# w5-MIDI_v03_rev4_4.net
KiCad netlist of a schematic drawn in EAGLE
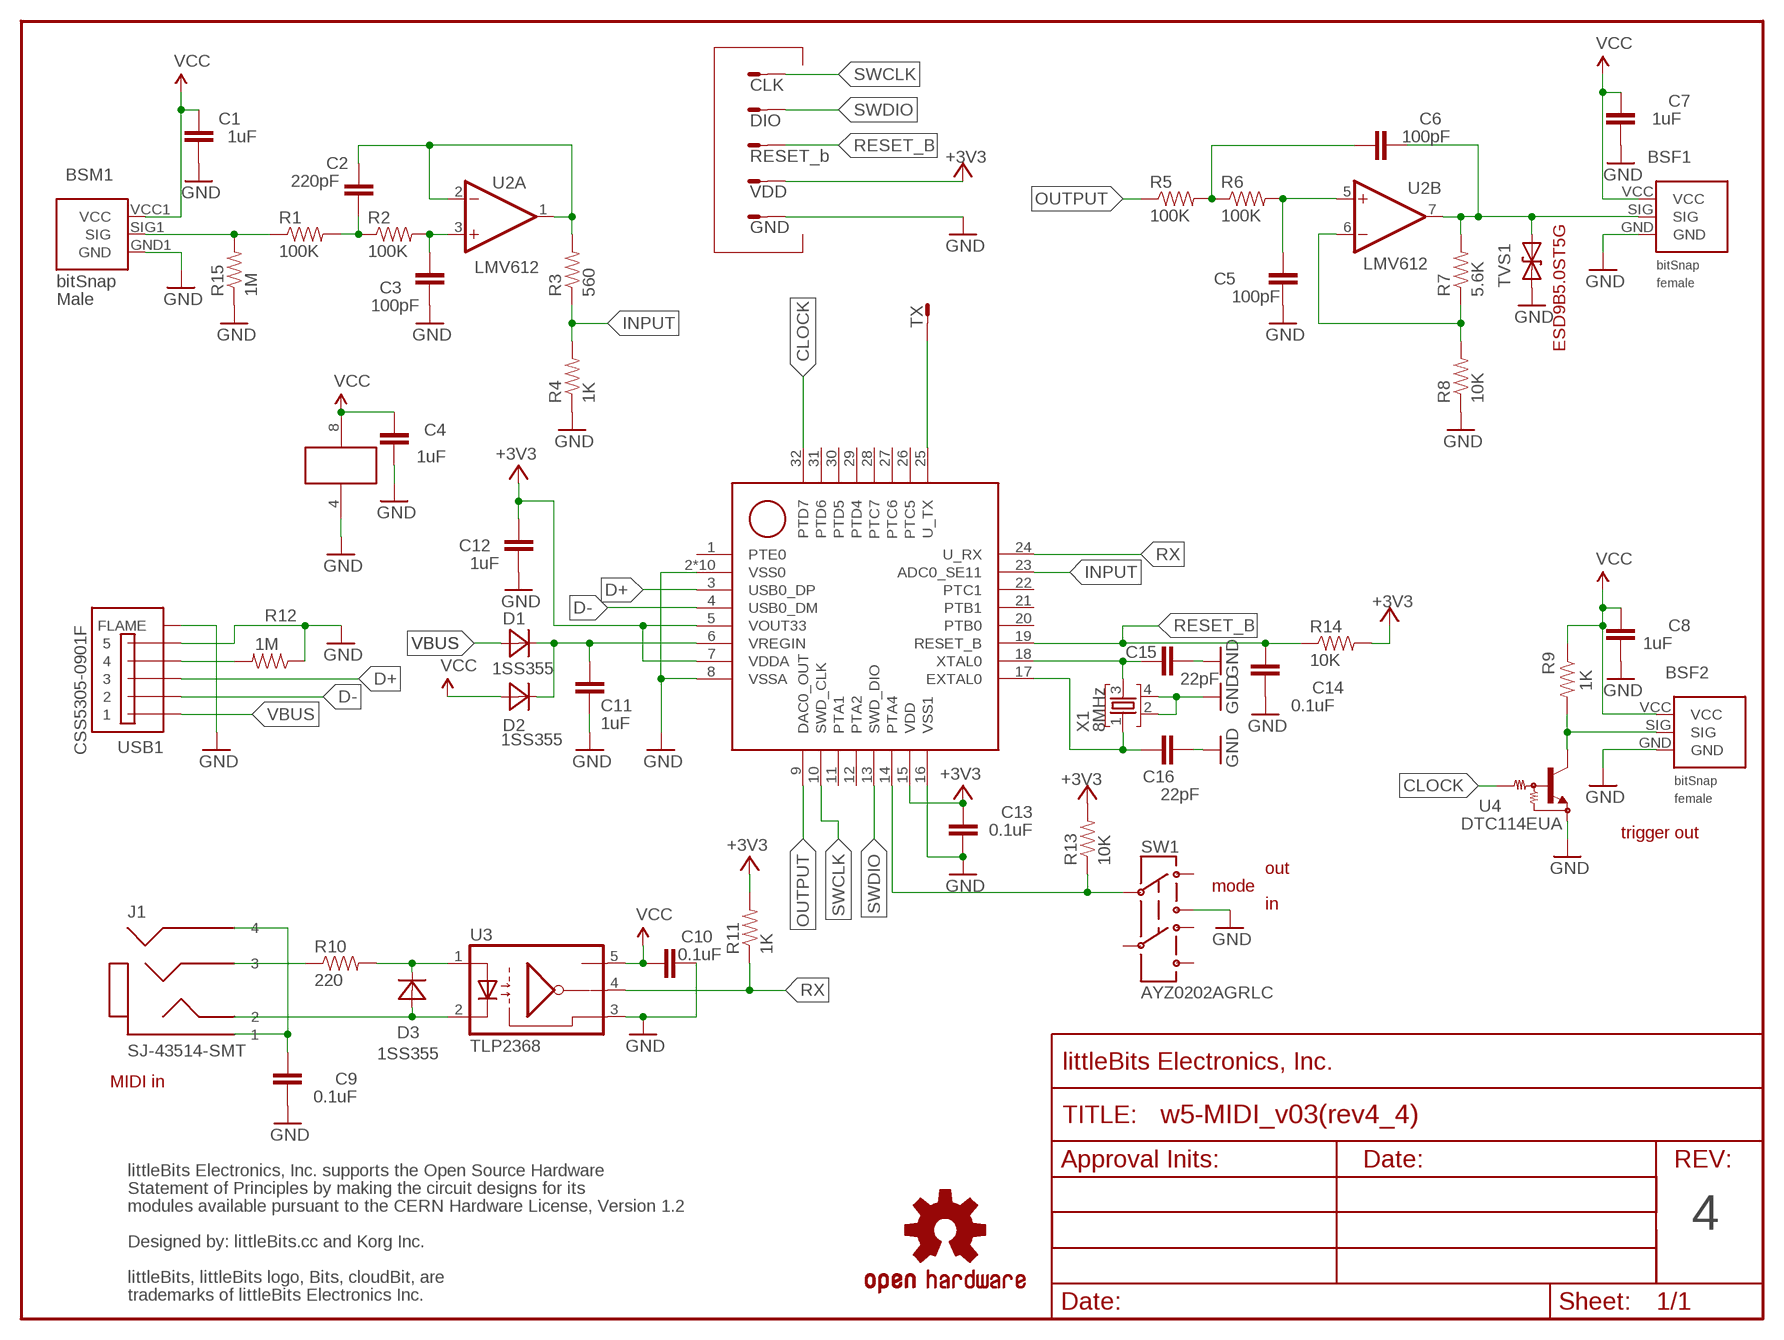
[diagram p0: schematic, sheet 1]

(export (version "E")
  (design (tool "Eeschema 10.0.6"))
  (components
    (comp (ref "BSF1")
      (value "BITSNAP_V03_FEMALE")
      (footprint "eagle-import:BITSNAP_V03_FEMALE")
      (libsource (lib "eagle-import") (part "BITSNAP_V03_FEMALE"))
    )
    (comp (ref "BSF2")
      (value "BITSNAP_V03_FEMALE")
      (footprint "eagle-import:BITSNAP_V03_FEMALE")
      (libsource (lib "eagle-import") (part "BITSNAP_V03_FEMALE"))
    )
    (comp (ref "BSM1")
      (value "BITSNAP_V03_MALE")
      (footprint "eagle-import:BITSNAP_V03_MALE")
      (libsource (lib "eagle-import") (part "BITSNAP_V03_MALE"))
    )
    (comp (ref "C1")
      (value "1uF")
      (footprint "eagle-import:CC_1608_0.8_TBR_LB_1PRIMARY")
      (libsource (lib "eagle-import") (part "CC_1608_0.8_TBR_LB_1"))
    )
    (comp (ref "C2")
      (value "220pF")
      (footprint "eagle-import:CC_1608_0.8_TBR_LB_1PRIMARY")
      (libsource (lib "eagle-import") (part "CC_1608_0.8_TBR_LB_1"))
    )
    (comp (ref "C3")
      (value "100pF")
      (footprint "eagle-import:CC_1608_0.8_TBR_LB_1PRIMARY")
      (libsource (lib "eagle-import") (part "CC_1608_0.8_TBR_LB_1"))
    )
    (comp (ref "C4")
      (value "1uF")
      (footprint "eagle-import:CC_1608_0.8_TBR_LB_1PRIMARY")
      (libsource (lib "eagle-import") (part "CC_1608_0.8_TBR_LB_1"))
    )
    (comp (ref "C5")
      (value "100pF")
      (footprint "eagle-import:CC_1608_0.8_TBR_LB_1PRIMARY")
      (libsource (lib "eagle-import") (part "CC_1608_0.8_TBR_LB_1"))
    )
    (comp (ref "C6")
      (value "100pF")
      (footprint "eagle-import:CC_1608_0.8_TBR_LB_1PRIMARY")
      (libsource (lib "eagle-import") (part "CC_1608_0.8_TBR_LB_1"))
    )
    (comp (ref "C7")
      (value "1uF")
      (footprint "eagle-import:CC_1608_0.8_TBR_LB_1PRIMARY")
      (libsource (lib "eagle-import") (part "CC_1608_0.8_TBR_LB_1"))
    )
    (comp (ref "C8")
      (value "1uF")
      (footprint "eagle-import:CC_1608_0.8_TBR_LB_1PRIMARY")
      (libsource (lib "eagle-import") (part "CC_1608_0.8_TBR_LB_1"))
    )
    (comp (ref "C9")
      (value "0.1uF")
      (footprint "eagle-import:CC_1608_0.8_TBR_LB_1PRIMARY")
      (libsource (lib "eagle-import") (part "CC_1608_0.8_TBR_LB_1"))
    )
    (comp (ref "C10")
      (value "0.1uF")
      (footprint "eagle-import:CC_1608_0.8_TBR_LB_1PRIMARY")
      (libsource (lib "eagle-import") (part "CC_1608_0.8_TBR_LB_1"))
    )
    (comp (ref "C11")
      (value "1uF")
      (footprint "eagle-import:CC_1608_0.8_TBR_LB_1PRIMARY")
      (libsource (lib "eagle-import") (part "CC_1608_0.8_TBR_LB_1"))
    )
    (comp (ref "C12")
      (value "1uF")
      (footprint "eagle-import:CC_1608_0.8_TBR_LB_1PRIMARY")
      (libsource (lib "eagle-import") (part "CC_1608_0.8_TBR_LB_1"))
    )
    (comp (ref "C13")
      (value "0.1uF")
      (footprint "eagle-import:CC_1608_0.8_TBR_LB_1PRIMARY")
      (libsource (lib "eagle-import") (part "CC_1608_0.8_TBR_LB_1"))
    )
    (comp (ref "C14")
      (value "0.1uF")
      (footprint "eagle-import:CC_1608_0.8_TBR_LB_1PRIMARY")
      (libsource (lib "eagle-import") (part "CC_1608_0.8_TBR_LB_1"))
    )
    (comp (ref "C15")
      (value "22pF")
      (footprint "eagle-import:CC_1608_0.8_TBR_LB_1PRIMARY")
      (libsource (lib "eagle-import") (part "CC_1608_0.8_TBR_LB_1"))
    )
    (comp (ref "C16")
      (value "22pF")
      (footprint "eagle-import:CC_1608_0.8_TBR_LB_1PRIMARY")
      (libsource (lib "eagle-import") (part "CC_1608_0.8_TBR_LB_1"))
    )
    (comp (ref "D1")
      (value "1SS355")
      (footprint "eagle-import:DISC_ROHM-UMD2_#_TBR_LB_1PRIMARY")
      (libsource (lib "eagle-import") (part "DISC_ROHM-UMD2_#_TBR_LB_1"))
    )
    (comp (ref "D2")
      (value "1SS355")
      (footprint "eagle-import:DISC_ROHM-UMD2_#_TBR_LB_1PRIMARY")
      (libsource (lib "eagle-import") (part "DISC_ROHM-UMD2_#_TBR_LB_1"))
    )
    (comp (ref "D3")
      (value "1SS355")
      (footprint "eagle-import:DISC_ROHM-UMD2_#_TBR_LB_1PRIMARY")
      (libsource (lib "eagle-import") (part "DISC_ROHM-UMD2_#_TBR_LB_1"))
    )
    (comp (ref "FRAME1")
      (value "FRAME-LETTER-OHWOHW")
      (footprint "eagle-import:FABDWG01-OHW")
      (libsource (lib "eagle-import") (part "FRAME-LETTER-OHWOHW"))
    )
    (comp (ref "J1")
      (value "SJ-43514-SMT")
      (footprint "eagle-import:LB_K_CN_SJ-43514-SMT_LB")
      (libsource (lib "eagle-import") (part "LB_K_CN_SJ-43514-SMT_LB"))
    )
    (comp (ref "R1")
      (value "100K")
      (footprint "eagle-import:R_1608_LB")
      (libsource (lib "eagle-import") (part "R_1608_LB"))
    )
    (comp (ref "R2")
      (value "100K")
      (footprint "eagle-import:R_1608_LB")
      (libsource (lib "eagle-import") (part "R_1608_LB"))
    )
    (comp (ref "R3")
      (value "560")
      (footprint "eagle-import:R_1608_LB")
      (libsource (lib "eagle-import") (part "R_1608_LB"))
    )
    (comp (ref "R4")
      (value "1K")
      (footprint "eagle-import:R_1608_LB")
      (libsource (lib "eagle-import") (part "R_1608_LB"))
    )
    (comp (ref "R5")
      (value "100K")
      (footprint "eagle-import:R_1608_LB")
      (libsource (lib "eagle-import") (part "R_1608_LB"))
    )
    (comp (ref "R6")
      (value "100K")
      (footprint "eagle-import:R_1608_LB")
      (libsource (lib "eagle-import") (part "R_1608_LB"))
    )
    (comp (ref "R7")
      (value "5.6K")
      (footprint "eagle-import:R_1608_LB")
      (libsource (lib "eagle-import") (part "R_1608_LB"))
    )
    (comp (ref "R8")
      (value "10K")
      (footprint "eagle-import:R_1608_LB")
      (libsource (lib "eagle-import") (part "R_1608_LB"))
    )
    (comp (ref "R9")
      (value "1K")
      (footprint "eagle-import:R_1608_LB")
      (libsource (lib "eagle-import") (part "R_1608_LB"))
    )
    (comp (ref "R10")
      (value "220")
      (footprint "eagle-import:R_1608_LB")
      (libsource (lib "eagle-import") (part "R_1608_LB"))
    )
    (comp (ref "R11")
      (value "1K")
      (footprint "eagle-import:R_1608_LB")
      (libsource (lib "eagle-import") (part "R_1608_LB"))
    )
    (comp (ref "R12")
      (value "1M")
      (footprint "eagle-import:R_1608_LB")
      (libsource (lib "eagle-import") (part "R_1608_LB"))
    )
    (comp (ref "R13")
      (value "10K")
      (footprint "eagle-import:R_1608_LB")
      (libsource (lib "eagle-import") (part "R_1608_LB"))
    )
    (comp (ref "R14")
      (value "10K")
      (footprint "eagle-import:R_1608_LB")
      (libsource (lib "eagle-import") (part "R_1608_LB"))
    )
    (comp (ref "R15")
      (value "1M")
      (footprint "eagle-import:RES-0402")
      (libsource (lib "eagle-import") (part "RESISTOR0402"))
    )
    (comp (ref "SW1")
      (value "AYZ0202AGRLC")
      (footprint "eagle-import:SW_MS-22C01_#_TBR_LB_1PRIMARY")
      (libsource (lib "eagle-import") (part "SW_MS-22C01_#_TBR_LB_1"))
    )
    (comp (ref "TVS1")
      (value "DIODE-TVSSOD-923")
      (footprint "eagle-import:SOD-923")
      (fields (field (name "MPN") "ESD9B5.0ST5G"))
      (libsource (lib "eagle-import") (part "DIODE-TVSSOD-923"))
    )
    (comp (ref "U$1")
      (value "OSHWCREDIT-KORG")
      (footprint "eagle-import:OSHWCREDIT-KORG")
      (libsource (lib "eagle-import") (part "OSHWCREDIT-KORG"))
    )
    (comp (ref "U$5")
      (value "OSHW-LOGOL")
      (footprint "eagle-import:OSHW-LOGO-L")
      (libsource (lib "eagle-import") (part "OSHW-LOGOL"))
    )
    (comp (ref "U1")
      (value "MKL26Z64VFM4")
      (footprint "eagle-import:IC_TI-QFN32_0.5_TBR_LB_1PRIMARY")
      (libsource (lib "eagle-import") (part "IC_TI-QFN32_0.5_TBR_LB_1"))
    )
    (comp (ref "U2")
      (value "LMV612")
      (footprint "eagle-import:IC_TSSOP8-DCK_0.65_TBR_LB_1PRIMARY")
      (libsource (lib "eagle-import") (part "IC_TSSOP8-DCK_0.65_TBR_LB_1"))
    )
    (comp (ref "U3")
      (value "TLP2368")
      (footprint "eagle-import:PC_PS9117-F3-A_#_TBR_LB_1PRIMARY")
      (libsource (lib "eagle-import") (part "PC_PS9117-F3-A_#_TBR_LB_1"))
    )
    (comp (ref "U4")
      (value "DTC114EUA")
      (footprint "eagle-import:DISC_SC-70_#_TBR_LB_1PRIMARY")
      (libsource (lib "eagle-import") (part "DISC_SC-70_#_TBR_LB_1"))
    )
    (comp (ref "USB1")
      (value "CSS5305-0901F")
      (footprint "eagle-import:MICRO-USB-FRONT-DIP-REAR-SMD")
      (libsource (lib "eagle-import") (part "CSS5305-0109F"))
    )
    (comp (ref "W5JP1")
      (value "GND")
      (footprint "eagle-import:TEST_POINT_1PRIMARY")
      (libsource (lib "eagle-import") (part "TEST_POINT_1"))
    )
    (comp (ref "W5JP2")
      (value "VDD")
      (footprint "eagle-import:TEST_POINT_1PRIMARY")
      (libsource (lib "eagle-import") (part "TEST_POINT_1"))
    )
    (comp (ref "W5JP3")
      (value "RESET_b")
      (footprint "eagle-import:TEST_POINT_1PRIMARY")
      (libsource (lib "eagle-import") (part "TEST_POINT_1"))
    )
    (comp (ref "W5JP4")
      (value "DIO")
      (footprint "eagle-import:TEST_POINT_1PRIMARY")
      (libsource (lib "eagle-import") (part "TEST_POINT_1"))
    )
    (comp (ref "W5JP5")
      (value "CLK")
      (footprint "eagle-import:TEST_POINT_1PRIMARY")
      (libsource (lib "eagle-import") (part "TEST_POINT_1"))
    )
    (comp (ref "W5JP6")
      (value "TX")
      (footprint "eagle-import:TEST_POINT_1PRIMARY")
      (libsource (lib "eagle-import") (part "TEST_POINT_1"))
    )
    (comp (ref "X1")
      (value "8MHz")
      (footprint "eagle-import:X_ROSON_RT5_#_TBR_LB_1PRIMARY")
      (libsource (lib "eagle-import") (part "X_ROSON_RT5_#_TBR_LB_1"))
    )
  )
  (nets
    (net (code "1") (name "+3V3") (class "Default")
      (node (ref "C12") (pin "2") (pinfunction "2_2") (pintype "passive"))
      (node (ref "C13") (pin "2") (pinfunction "2_2") (pintype "passive"))
      (node (ref "R11") (pin "2") (pinfunction "2_2") (pintype "passive"))
      (node (ref "R13") (pin "2") (pinfunction "2_2") (pintype "passive"))
      (node (ref "R14") (pin "2") (pinfunction "2_2") (pintype "passive"))
      (node (ref "U1") (pin "15") (pinfunction "VDD_15") (pintype "bidirectional"))
      (node (ref "U1") (pin "5") (pinfunction "VOUT33_5") (pintype "bidirectional"))
      (node (ref "U1") (pin "7") (pinfunction "VDDA_7") (pintype "bidirectional"))
      (node (ref "W5JP2") (pin "1") (pinfunction "S_1") (pintype "passive"))
    )
    (net (code "2") (name "CLOCK") (class "Default")
      (node (ref "U1") (pin "32") (pinfunction "PTD7_32") (pintype "bidirectional"))
      (node (ref "U4") (pin "1") (pinfunction "B_1") (pintype "passive"))
    )
    (net (code "3") (name "D+") (class "Default")
      (node (ref "U1") (pin "3") (pinfunction "USB0_DP_3") (pintype "bidirectional"))
      (node (ref "USB1") (pin "3") (pinfunction "3_3") (pintype "input"))
    )
    (net (code "4") (name "D-") (class "Default")
      (node (ref "U1") (pin "4") (pinfunction "USB0_DM_4") (pintype "bidirectional"))
      (node (ref "USB1") (pin "2") (pinfunction "2_2") (pintype "input"))
    )
    (net (code "5") (name "GND") (class "Default")
      (node (ref "BSF1") (pin "GND") (pinfunction "GND_GND") (pintype "bidirectional"))
      (node (ref "BSF2") (pin "GND") (pinfunction "GND_GND") (pintype "bidirectional"))
      (node (ref "BSM1") (pin "GND1") (pinfunction "GND_GND1") (pintype "bidirectional"))
      (node (ref "C1") (pin "2") (pinfunction "2_2") (pintype "passive"))
      (node (ref "C10") (pin "2") (pinfunction "2_2") (pintype "passive"))
      (node (ref "C11") (pin "2") (pinfunction "2_2") (pintype "passive"))
      (node (ref "C12") (pin "1") (pinfunction "1_1") (pintype "passive"))
      (node (ref "C13") (pin "1") (pinfunction "1_1") (pintype "passive"))
      (node (ref "C14") (pin "1") (pinfunction "1_1") (pintype "passive"))
      (node (ref "C15") (pin "1") (pinfunction "1_1") (pintype "passive"))
      (node (ref "C16") (pin "1") (pinfunction "1_1") (pintype "passive"))
      (node (ref "C3") (pin "1") (pinfunction "1_1") (pintype "passive"))
      (node (ref "C4") (pin "1") (pinfunction "1_1") (pintype "passive"))
      (node (ref "C5") (pin "1") (pinfunction "1_1") (pintype "passive"))
      (node (ref "C7") (pin "1") (pinfunction "1_1") (pintype "passive"))
      (node (ref "C8") (pin "1") (pinfunction "1_1") (pintype "passive"))
      (node (ref "C9") (pin "1") (pinfunction "1_1") (pintype "passive"))
      (node (ref "R12") (pin "1") (pinfunction "1_1") (pintype "passive"))
      (node (ref "R15") (pin "1") (pinfunction "1_1") (pintype "passive"))
      (node (ref "R4") (pin "1") (pinfunction "1_1") (pintype "passive"))
      (node (ref "R8") (pin "1") (pinfunction "1_1") (pintype "passive"))
      (node (ref "SW1") (pin "3") (pinfunction "3_3") (pintype "bidirectional"))
      (node (ref "TVS1") (pin "1") (pinfunction "A_1") (pintype "passive"))
      (node (ref "U1") (pin "16") (pinfunction "VSS1_16") (pintype "bidirectional"))
      (node (ref "U1") (pin "2") (pinfunction "VSS0_2") (pintype "bidirectional"))
      (node (ref "U1") (pin "33") (pinfunction "VSS0_33") (pintype "bidirectional"))
      (node (ref "U1") (pin "34") (pinfunction "VSS0_34") (pintype "bidirectional"))
      (node (ref "U1") (pin "35") (pinfunction "VSS0_35") (pintype "bidirectional"))
      (node (ref "U1") (pin "36") (pinfunction "VSS0_36") (pintype "bidirectional"))
      (node (ref "U1") (pin "37") (pinfunction "VSS0_37") (pintype "bidirectional"))
      (node (ref "U1") (pin "38") (pinfunction "VSS0_38") (pintype "bidirectional"))
      (node (ref "U1") (pin "39") (pinfunction "VSS0_39") (pintype "bidirectional"))
      (node (ref "U1") (pin "40") (pinfunction "VSS0_40") (pintype "bidirectional"))
      (node (ref "U1") (pin "41") (pinfunction "VSS0_41") (pintype "bidirectional"))
      (node (ref "U1") (pin "8") (pinfunction "VSSA_8") (pintype "bidirectional"))
      (node (ref "U2") (pin "4") (pinfunction "V-_4") (pintype "power_in"))
      (node (ref "U3") (pin "3") (pinfunction "GND_3") (pintype "passive"))
      (node (ref "U4") (pin "2") (pinfunction "E_2") (pintype "passive"))
      (node (ref "USB1") (pin "10") (pinfunction "FLAME_10") (pintype "power_in"))
      (node (ref "USB1") (pin "11") (pinfunction "FLAME_11") (pintype "power_in"))
      (node (ref "USB1") (pin "5") (pinfunction "5_5") (pintype "input"))
      (node (ref "USB1") (pin "6") (pinfunction "FLAME_6") (pintype "power_in"))
      (node (ref "USB1") (pin "7") (pinfunction "FLAME_7") (pintype "power_in"))
      (node (ref "USB1") (pin "8") (pinfunction "FLAME_8") (pintype "power_in"))
      (node (ref "USB1") (pin "9") (pinfunction "FLAME_9") (pintype "power_in"))
      (node (ref "W5JP1") (pin "1") (pinfunction "S_1") (pintype "passive"))
      (node (ref "X1") (pin "2") (pinfunction "2_2") (pintype "passive"))
      (node (ref "X1") (pin "4") (pinfunction "4_4") (pintype "passive"))
    )
    (net (code "6") (name "INPUT") (class "Default")
      (node (ref "R3") (pin "1") (pinfunction "1_1") (pintype "passive"))
      (node (ref "R4") (pin "2") (pinfunction "2_2") (pintype "passive"))
      (node (ref "U1") (pin "23") (pinfunction "ADC0_SE11_23") (pintype "bidirectional"))
    )
    (net (code "7") (name "Net-(BSM1-SIG)") (class "Default")
      (node (ref "BSM1") (pin "SIG1") (pinfunction "SIG_SIG1") (pintype "bidirectional"))
      (node (ref "R1") (pin "1") (pinfunction "1_1") (pintype "passive"))
      (node (ref "R15") (pin "2") (pinfunction "2_2") (pintype "passive"))
    )
    (net (code "8") (name "Net-(C2-Pad1)") (class "Default")
      (node (ref "C2") (pin "1") (pinfunction "1_1") (pintype "passive"))
      (node (ref "R1") (pin "2") (pinfunction "2_2") (pintype "passive"))
      (node (ref "R2") (pin "1") (pinfunction "1_1") (pintype "passive"))
    )
    (net (code "9") (name "Net-(C6-Pad2)") (class "Default")
      (node (ref "C6") (pin "2") (pinfunction "2_2") (pintype "passive"))
      (node (ref "R5") (pin "2") (pinfunction "2_2") (pintype "passive"))
      (node (ref "R6") (pin "1") (pinfunction "1_1") (pintype "passive"))
    )
    (net (code "10") (name "Net-(C9-Pad2)") (class "Default")
      (node (ref "C9") (pin "2") (pinfunction "2_2") (pintype "passive"))
      (node (ref "J1") (pin "1") (pinfunction "1_1") (pintype "bidirectional"))
      (node (ref "J1") (pin "4") (pinfunction "4_4") (pintype "bidirectional"))
    )
    (net (code "11") (name "Net-(J1-Pad3)") (class "Default")
      (node (ref "J1") (pin "3") (pinfunction "3_3") (pintype "bidirectional"))
      (node (ref "R10") (pin "1") (pinfunction "1_1") (pintype "passive"))
    )
    (net (code "12") (name "Net-(R12-Pad2)") (class "Default")
      (node (ref "R12") (pin "2") (pinfunction "2_2") (pintype "passive"))
      (node (ref "USB1") (pin "4") (pinfunction "4_4") (pintype "input"))
    )
    (net (code "13") (name "Net-(TVS1-C)") (class "Default")
      (node (ref "BSF1") (pin "SIG") (pinfunction "SIG_SIG") (pintype "bidirectional"))
      (node (ref "C6") (pin "1") (pinfunction "1_1") (pintype "passive"))
      (node (ref "R7") (pin "2") (pinfunction "2_2") (pintype "passive"))
      (node (ref "TVS1") (pin "2") (pinfunction "C_2") (pintype "passive"))
      (node (ref "U2") (pin "7") (pinfunction "OUT_7") (pintype "output"))
    )
    (net (code "14") (name "Net-(U1-EXTAL0)") (class "Default")
      (node (ref "C16") (pin "2") (pinfunction "2_2") (pintype "passive"))
      (node (ref "U1") (pin "17") (pinfunction "EXTAL0_17") (pintype "bidirectional"))
      (node (ref "X1") (pin "1") (pinfunction "1_1") (pintype "passive"))
    )
    (net (code "15") (name "Net-(U1-PTA4)") (class "Default")
      (node (ref "R13") (pin "1") (pinfunction "1_1") (pintype "passive"))
      (node (ref "SW1") (pin "2") (pinfunction "2_2") (pintype "bidirectional"))
      (node (ref "U1") (pin "14") (pinfunction "PTA4_14") (pintype "bidirectional"))
    )
    (net (code "16") (name "Net-(U1-U_TX)") (class "Default")
      (node (ref "U1") (pin "25") (pinfunction "U_TX_25") (pintype "bidirectional"))
      (node (ref "W5JP6") (pin "1") (pinfunction "S_1") (pintype "passive"))
    )
    (net (code "17") (name "Net-(U1-VREGIN)") (class "Default")
      (node (ref "C11") (pin "1") (pinfunction "1_1") (pintype "passive"))
      (node (ref "D1") (pin "2") (pinfunction "2_2") (pintype "passive"))
      (node (ref "D2") (pin "2") (pinfunction "2_2") (pintype "passive"))
      (node (ref "U1") (pin "6") (pinfunction "VREGIN_6") (pintype "bidirectional"))
    )
    (net (code "18") (name "Net-(U1-XTAL0)") (class "Default")
      (node (ref "C15") (pin "2") (pinfunction "2_2") (pintype "passive"))
      (node (ref "U1") (pin "18") (pinfunction "XTAL0_18") (pintype "bidirectional"))
      (node (ref "X1") (pin "3") (pinfunction "3_3") (pintype "passive"))
    )
    (net (code "19") (name "Net-(U2A-+IN)") (class "Default")
      (node (ref "C3") (pin "2") (pinfunction "2_2") (pintype "passive"))
      (node (ref "R2") (pin "2") (pinfunction "2_2") (pintype "passive"))
      (node (ref "U2") (pin "3") (pinfunction "+IN_3") (pintype "input"))
    )
    (net (code "20") (name "Net-(U2A--IN)") (class "Default")
      (node (ref "C2") (pin "2") (pinfunction "2_2") (pintype "passive"))
      (node (ref "R3") (pin "2") (pinfunction "2_2") (pintype "passive"))
      (node (ref "U2") (pin "1") (pinfunction "OUT_1") (pintype "output"))
      (node (ref "U2") (pin "2") (pinfunction "-IN_2") (pintype "input"))
    )
    (net (code "21") (name "Net-(U2B-+IN)") (class "Default")
      (node (ref "C5") (pin "2") (pinfunction "2_2") (pintype "passive"))
      (node (ref "R6") (pin "2") (pinfunction "2_2") (pintype "passive"))
      (node (ref "U2") (pin "5") (pinfunction "+IN_5") (pintype "input"))
    )
    (net (code "22") (name "Net-(U2B--IN)") (class "Default")
      (node (ref "R7") (pin "1") (pinfunction "1_1") (pintype "passive"))
      (node (ref "R8") (pin "2") (pinfunction "2_2") (pintype "passive"))
      (node (ref "U2") (pin "6") (pinfunction "-IN_6") (pintype "input"))
    )
    (net (code "23") (name "Net-(U3-A)") (class "Default")
      (node (ref "D3") (pin "2") (pinfunction "2_2") (pintype "passive"))
      (node (ref "R10") (pin "2") (pinfunction "2_2") (pintype "passive"))
      (node (ref "U3") (pin "1") (pinfunction "A_1") (pintype "passive"))
    )
    (net (code "24") (name "Net-(U3-C)") (class "Default")
      (node (ref "D3") (pin "1") (pinfunction "1_1") (pintype "passive"))
      (node (ref "J1") (pin "2") (pinfunction "2_2") (pintype "bidirectional"))
      (node (ref "U3") (pin "2") (pinfunction "C_2") (pintype "passive"))
    )
    (net (code "25") (name "Net-(U4-C)") (class "Default")
      (node (ref "BSF2") (pin "SIG") (pinfunction "SIG_SIG") (pintype "bidirectional"))
      (node (ref "R9") (pin "2") (pinfunction "2_2") (pintype "passive"))
      (node (ref "U4") (pin "3") (pinfunction "C_3") (pintype "passive"))
    )
    (net (code "26") (name "OUTPUT") (class "Default")
      (node (ref "R5") (pin "1") (pinfunction "1_1") (pintype "passive"))
      (node (ref "U1") (pin "9") (pinfunction "DAC0_OUT_9") (pintype "bidirectional"))
    )
    (net (code "27") (name "RESET_B") (class "Default")
      (node (ref "C14") (pin "2") (pinfunction "2_2") (pintype "passive"))
      (node (ref "R14") (pin "1") (pinfunction "1_1") (pintype "passive"))
      (node (ref "U1") (pin "19") (pinfunction "RESET_B_19") (pintype "bidirectional"))
      (node (ref "W5JP3") (pin "1") (pinfunction "S_1") (pintype "passive"))
    )
    (net (code "28") (name "RX") (class "Default")
      (node (ref "R11") (pin "1") (pinfunction "1_1") (pintype "passive"))
      (node (ref "U1") (pin "24") (pinfunction "U_RX_24") (pintype "bidirectional"))
      (node (ref "U3") (pin "4") (pinfunction "VO_4") (pintype "passive"))
    )
    (net (code "29") (name "SWCLK") (class "Default")
      (node (ref "U1") (pin "10") (pinfunction "SWD_CLK_10") (pintype "bidirectional"))
      (node (ref "W5JP5") (pin "1") (pinfunction "S_1") (pintype "passive"))
    )
    (net (code "30") (name "SWDIO") (class "Default")
      (node (ref "U1") (pin "13") (pinfunction "SWD_DIO_13") (pintype "bidirectional"))
      (node (ref "W5JP4") (pin "1") (pinfunction "S_1") (pintype "passive"))
    )
    (net (code "31") (name "VBUS") (class "Default")
      (node (ref "D1") (pin "1") (pinfunction "1_1") (pintype "passive"))
      (node (ref "USB1") (pin "1") (pinfunction "1_1") (pintype "input"))
    )
    (net (code "32") (name "VCC") (class "Default")
      (node (ref "BSF1") (pin "VCC") (pinfunction "VCC_VCC") (pintype "bidirectional"))
      (node (ref "BSF2") (pin "VCC") (pinfunction "VCC_VCC") (pintype "bidirectional"))
      (node (ref "BSM1") (pin "VCC1") (pinfunction "VCC_VCC1") (pintype "bidirectional"))
      (node (ref "C1") (pin "1") (pinfunction "1_1") (pintype "passive"))
      (node (ref "C10") (pin "1") (pinfunction "1_1") (pintype "passive"))
      (node (ref "C4") (pin "2") (pinfunction "2_2") (pintype "passive"))
      (node (ref "C7") (pin "2") (pinfunction "2_2") (pintype "passive"))
      (node (ref "C8") (pin "2") (pinfunction "2_2") (pintype "passive"))
      (node (ref "D2") (pin "1") (pinfunction "1_1") (pintype "passive"))
      (node (ref "R9") (pin "1") (pinfunction "1_1") (pintype "passive"))
      (node (ref "U2") (pin "8") (pinfunction "V+_8") (pintype "power_in"))
      (node (ref "U3") (pin "5") (pinfunction "VCC_5") (pintype "passive"))
    )
    (net (code "33") (name "unconnected-(SW1-Pad1)") (class "Default")
      (node (ref "SW1") (pin "1") (pinfunction "1_1") (pintype "bidirectional"))
    )
    (net (code "34") (name "unconnected-(SW1-Pad4)") (class "Default")
      (node (ref "SW1") (pin "4") (pinfunction "4_4") (pintype "bidirectional"))
    )
    (net (code "35") (name "unconnected-(SW1-Pad5)") (class "Default")
      (node (ref "SW1") (pin "5") (pinfunction "5_5") (pintype "bidirectional"))
    )
    (net (code "36") (name "unconnected-(SW1-Pad6)") (class "Default")
      (node (ref "SW1") (pin "6") (pinfunction "6_6") (pintype "bidirectional"))
    )
    (net (code "37") (name "unconnected-(U1-PTA1-Pad11)") (class "Default")
      (node (ref "U1") (pin "11") (pinfunction "PTA1_11") (pintype "bidirectional"))
    )
    (net (code "38") (name "unconnected-(U1-PTA2-Pad12)") (class "Default")
      (node (ref "U1") (pin "12") (pinfunction "PTA2_12") (pintype "bidirectional"))
    )
    (net (code "39") (name "unconnected-(U1-PTB0-Pad20)") (class "Default")
      (node (ref "U1") (pin "20") (pinfunction "PTB0_20") (pintype "bidirectional"))
    )
    (net (code "40") (name "unconnected-(U1-PTB1-Pad21)") (class "Default")
      (node (ref "U1") (pin "21") (pinfunction "PTB1_21") (pintype "bidirectional"))
    )
    (net (code "41") (name "unconnected-(U1-PTC1-Pad22)") (class "Default")
      (node (ref "U1") (pin "22") (pinfunction "PTC1_22") (pintype "bidirectional"))
    )
    (net (code "42") (name "unconnected-(U1-PTC5-Pad26)") (class "Default")
      (node (ref "U1") (pin "26") (pinfunction "PTC5_26") (pintype "bidirectional"))
    )
    (net (code "43") (name "unconnected-(U1-PTC6-Pad27)") (class "Default")
      (node (ref "U1") (pin "27") (pinfunction "PTC6_27") (pintype "bidirectional"))
    )
    (net (code "44") (name "unconnected-(U1-PTC7-Pad28)") (class "Default")
      (node (ref "U1") (pin "28") (pinfunction "PTC7_28") (pintype "bidirectional"))
    )
    (net (code "45") (name "unconnected-(U1-PTD4-Pad29)") (class "Default")
      (node (ref "U1") (pin "29") (pinfunction "PTD4_29") (pintype "bidirectional"))
    )
    (net (code "46") (name "unconnected-(U1-PTD5-Pad30)") (class "Default")
      (node (ref "U1") (pin "30") (pinfunction "PTD5_30") (pintype "bidirectional"))
    )
    (net (code "47") (name "unconnected-(U1-PTD6-Pad31)") (class "Default")
      (node (ref "U1") (pin "31") (pinfunction "PTD6_31") (pintype "bidirectional"))
    )
    (net (code "48") (name "unconnected-(U1-PTE0-Pad1)") (class "Default")
      (node (ref "U1") (pin "1") (pinfunction "PTE0_1") (pintype "bidirectional"))
    )
  )
)
